# test1.net
KiCad netlist of a schematic drawn in EAGLE
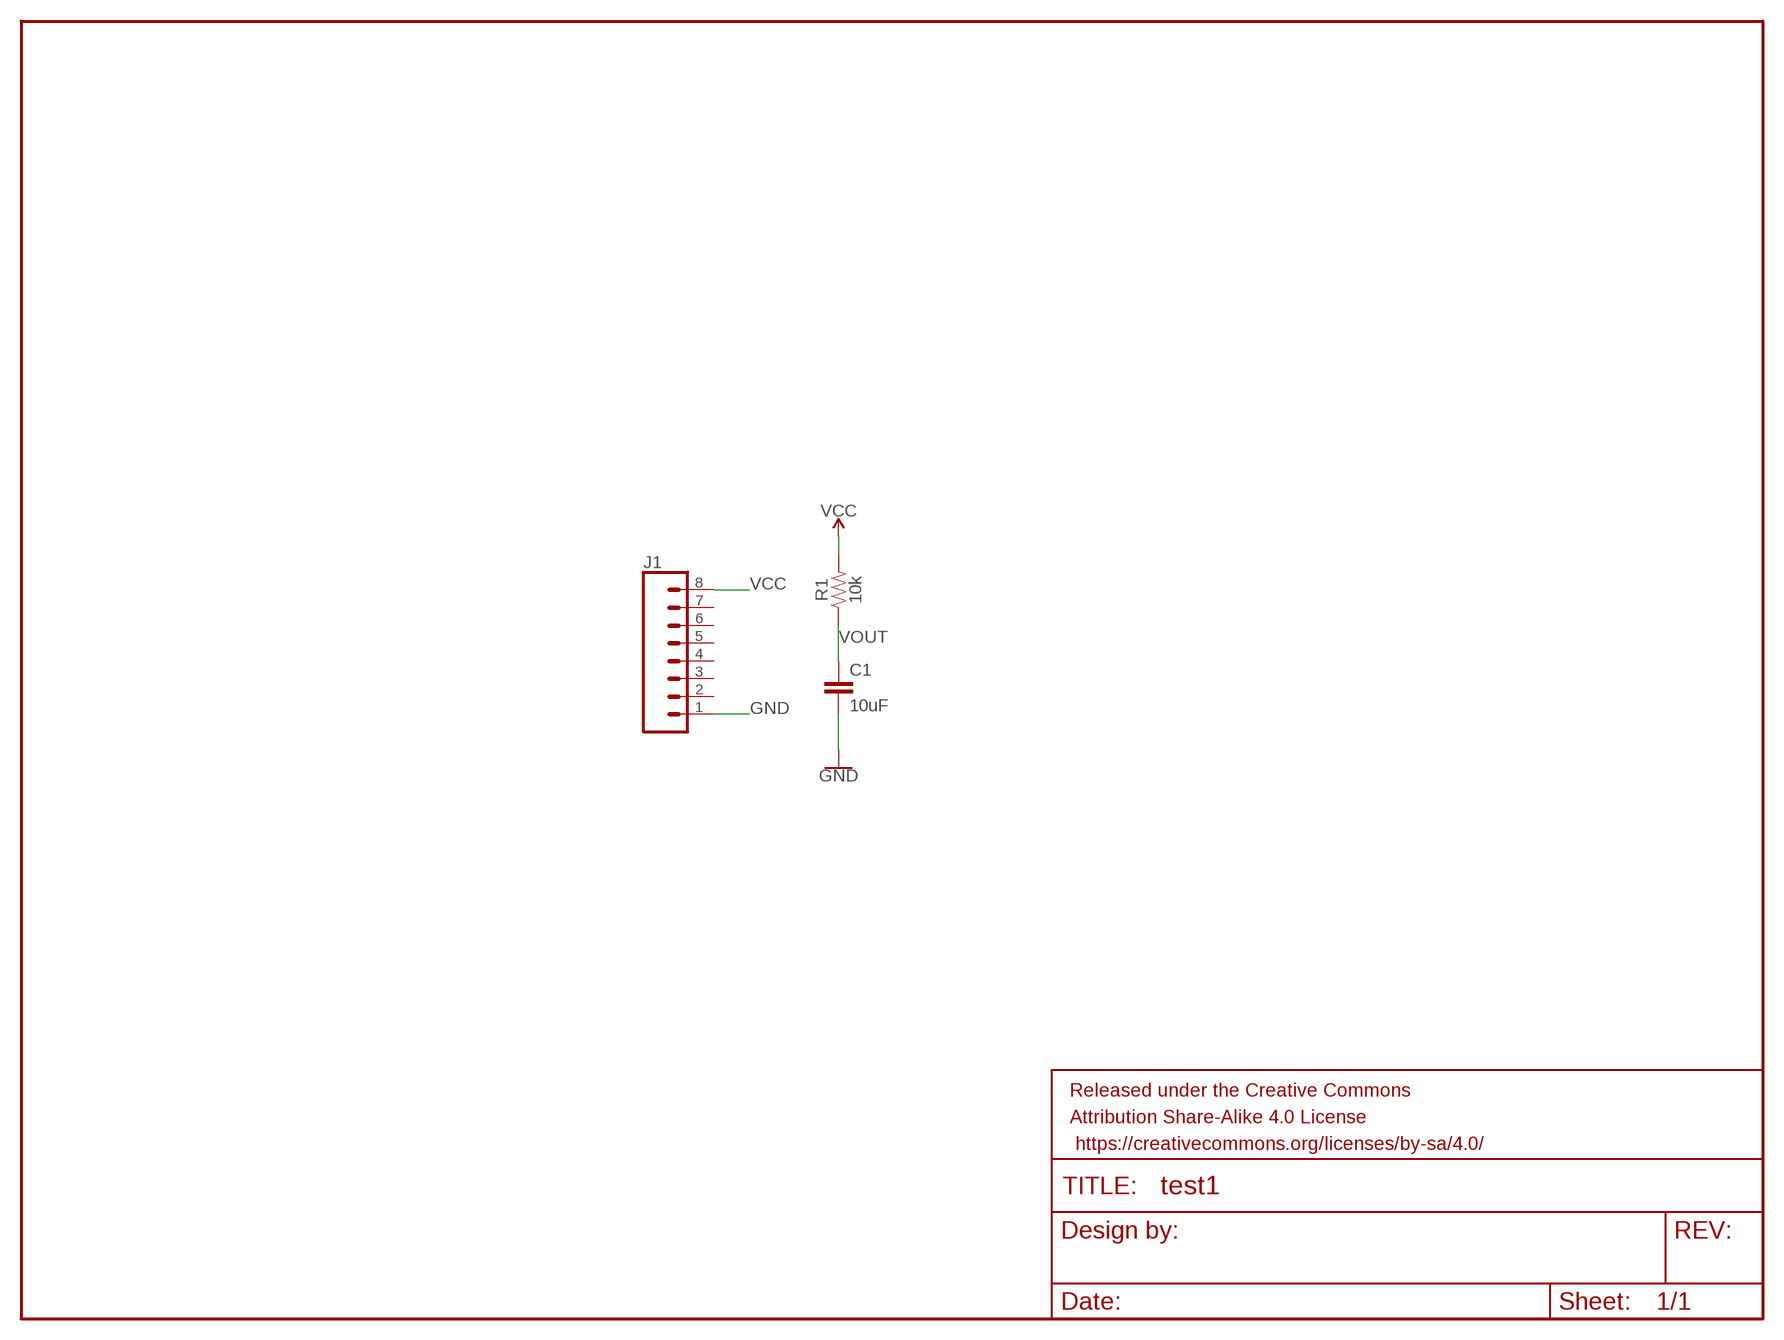
[diagram p0: schematic, sheet 1]

(export (version "E")
  (design (tool "Eeschema 10.0.6"))
  (components
    (comp (ref "C1")
      (value "10uF")
      (footprint "eagle-import:CAP-PTH-SMALL-KIT")
      (libsource (lib "eagle-import") (part "0.1UF-KIT-EZ-50V-20%"))
    )
    (comp (ref "FRAME1")
      (value "FRAME-LETTER")
      (footprint "eagle-import:CREATIVE_COMMONS")
      (libsource (lib "eagle-import") (part "FRAME-LETTER"))
    )
    (comp (ref "J1")
      (value "CONN_08\"")
      (footprint "eagle-import:1X08")
      (libsource (lib "eagle-import") (part "CONN_08{dblquote}"))
    )
    (comp (ref "R1")
      (value "10k")
      (footprint "eagle-import:0805")
      (libsource (lib "eagle-import") (part "0.3OHM-0805-1/8W-1%"))
    )
  )
  (nets
    (net (code "1") (name "/VOUT") (class "Default")
      (node (ref "C1") (pin "1") (pinfunction "1_1") (pintype "passive"))
      (node (ref "R1") (pin "1") (pinfunction "1_1") (pintype "passive"))
    )
    (net (code "2") (name "GND") (class "Default")
      (node (ref "C1") (pin "2") (pinfunction "2_2") (pintype "passive"))
      (node (ref "J1") (pin "1") (pinfunction "1_1") (pintype "passive"))
    )
    (net (code "3") (name "VCC") (class "Default")
      (node (ref "J1") (pin "8") (pinfunction "8_8") (pintype "passive"))
      (node (ref "R1") (pin "2") (pinfunction "2_2") (pintype "passive"))
    )
    (net (code "4") (name "unconnected-(J1-Pad2)") (class "Default")
      (node (ref "J1") (pin "2") (pinfunction "2_2") (pintype "passive"))
    )
    (net (code "5") (name "unconnected-(J1-Pad3)") (class "Default")
      (node (ref "J1") (pin "3") (pinfunction "3_3") (pintype "passive"))
    )
    (net (code "6") (name "unconnected-(J1-Pad4)") (class "Default")
      (node (ref "J1") (pin "4") (pinfunction "4_4") (pintype "passive"))
    )
    (net (code "7") (name "unconnected-(J1-Pad5)") (class "Default")
      (node (ref "J1") (pin "5") (pinfunction "5_5") (pintype "passive"))
    )
    (net (code "8") (name "unconnected-(J1-Pad6)") (class "Default")
      (node (ref "J1") (pin "6") (pinfunction "6_6") (pintype "passive"))
    )
    (net (code "9") (name "unconnected-(J1-Pad7)") (class "Default")
      (node (ref "J1") (pin "7") (pinfunction "7_7") (pintype "passive"))
    )
  )
)
